# Adapter-IO4-test.net
KiCad netlist of a schematic drawn in EAGLE
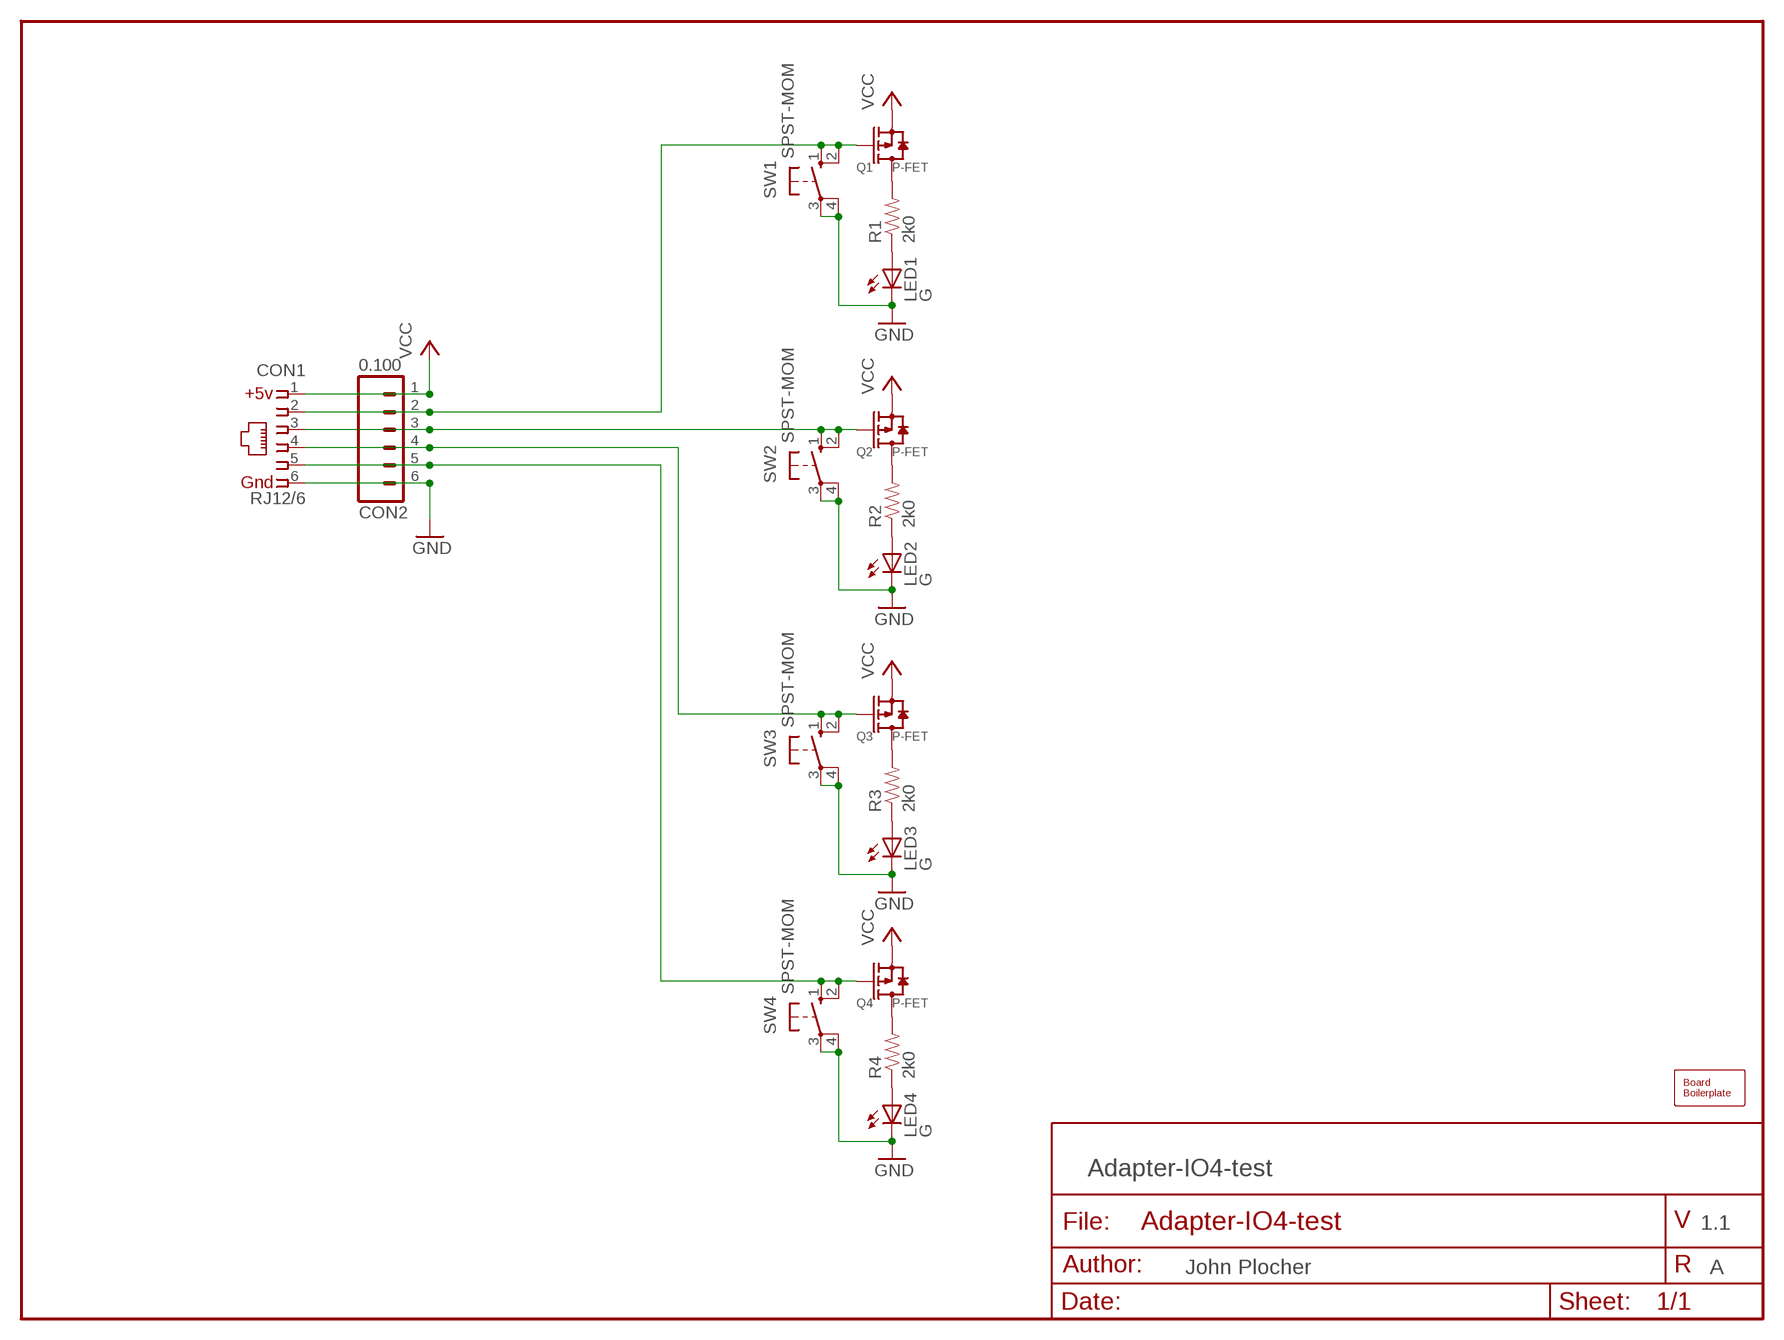
[diagram p0: schematic, sheet 1]

(export (version "E")
  (design (tool "Eeschema 10.0.6"))
  (components
    (comp (ref "BOARD1")
      (value "BOARD50X50-NOHOLES")
      (footprint "eagle-import:BOARD-SEEED5X5-NOHOLES")
      (libsource (lib "eagle-import") (part "BOARD50X50-NOHOLES"))
    )
    (comp (ref "CON1")
      (value "RJ12/6")
      (footprint "eagle-import:RJ25-INVERTED")
      (libsource (lib "eagle-import") (part "CONNECTOR-IO4INV"))
    )
    (comp (ref "CON2")
      (value "0.100")
      (footprint "eagle-import:1X06_LOCK")
      (libsource (lib "eagle-import") (part "CONNECTOR-M06LOCK"))
    )
    (comp (ref "LED1")
      (value "G")
      (footprint "eagle-import:0603-LED")
      (libsource (lib "eagle-import") (part "LED0603-LED"))
    )
    (comp (ref "LED2")
      (value "G")
      (footprint "eagle-import:0603-LED")
      (libsource (lib "eagle-import") (part "LED0603-LED"))
    )
    (comp (ref "LED3")
      (value "G")
      (footprint "eagle-import:0603-LED")
      (libsource (lib "eagle-import") (part "LED0603-LED"))
    )
    (comp (ref "LED4")
      (value "G")
      (footprint "eagle-import:0603-LED")
      (libsource (lib "eagle-import") (part "LED0603-LED"))
    )
    (comp (ref "Q1")
      (value "P-FET")
      (footprint "eagle-import:SOT23-3")
      (libsource (lib "eagle-import") (part "MOSFET-P"))
    )
    (comp (ref "Q2")
      (value "P-FET")
      (footprint "eagle-import:SOT23-3")
      (libsource (lib "eagle-import") (part "MOSFET-P"))
    )
    (comp (ref "Q3")
      (value "P-FET")
      (footprint "eagle-import:SOT23-3")
      (libsource (lib "eagle-import") (part "MOSFET-P"))
    )
    (comp (ref "Q4")
      (value "P-FET")
      (footprint "eagle-import:SOT23-3")
      (libsource (lib "eagle-import") (part "MOSFET-P"))
    )
    (comp (ref "R1")
      (value "2k0")
      (footprint "eagle-import:0603-RES")
      (libsource (lib "eagle-import") (part "R0603-RES"))
    )
    (comp (ref "R2")
      (value "2k0")
      (footprint "eagle-import:0603-RES")
      (libsource (lib "eagle-import") (part "R0603-RES"))
    )
    (comp (ref "R3")
      (value "2k0")
      (footprint "eagle-import:0603-RES")
      (libsource (lib "eagle-import") (part "R0603-RES"))
    )
    (comp (ref "R4")
      (value "2k0")
      (footprint "eagle-import:0603-RES")
      (libsource (lib "eagle-import") (part "R0603-RES"))
    )
    (comp (ref "SW1")
      (value "SPST-MOM")
      (footprint "eagle-import:B3F-10XX")
      (libsource (lib "eagle-import") (part "SWITCH-10-XX"))
    )
    (comp (ref "SW2")
      (value "SPST-MOM")
      (footprint "eagle-import:B3F-10XX")
      (libsource (lib "eagle-import") (part "SWITCH-10-XX"))
    )
    (comp (ref "SW3")
      (value "SPST-MOM")
      (footprint "eagle-import:B3F-10XX")
      (libsource (lib "eagle-import") (part "SWITCH-10-XX"))
    )
    (comp (ref "SW4")
      (value "SPST-MOM")
      (footprint "eagle-import:B3F-10XX")
      (libsource (lib "eagle-import") (part "SWITCH-10-XX"))
    )
  )
  (nets
    (net (code "1") (name "GND") (class "Default")
      (node (ref "CON1") (pin "6") (pinfunction "6_6") (pintype "power_in"))
      (node (ref "CON2") (pin "6") (pinfunction "6_6") (pintype "passive"))
      (node (ref "LED1") (pin "C") (pinfunction "C_C") (pintype "passive"))
      (node (ref "LED2") (pin "C") (pinfunction "C_C") (pintype "passive"))
      (node (ref "LED3") (pin "C") (pinfunction "C_C") (pintype "passive"))
      (node (ref "LED4") (pin "C") (pinfunction "C_C") (pintype "passive"))
      (node (ref "SW1") (pin "3") (pinfunction "P_3") (pintype "passive"))
      (node (ref "SW1") (pin "4") (pinfunction "P1_4") (pintype "passive"))
      (node (ref "SW2") (pin "3") (pinfunction "P_3") (pintype "passive"))
      (node (ref "SW2") (pin "4") (pinfunction "P1_4") (pintype "passive"))
      (node (ref "SW3") (pin "3") (pinfunction "P_3") (pintype "passive"))
      (node (ref "SW3") (pin "4") (pinfunction "P1_4") (pintype "passive"))
      (node (ref "SW4") (pin "3") (pinfunction "P_3") (pintype "passive"))
      (node (ref "SW4") (pin "4") (pinfunction "P1_4") (pintype "passive"))
    )
    (net (code "2") (name "Net-(LED1-PadA)") (class "Default")
      (node (ref "LED1") (pin "A") (pinfunction "A_A") (pintype "passive"))
      (node (ref "R1") (pin "1") (pinfunction "1_1") (pintype "passive"))
    )
    (net (code "3") (name "Net-(LED2-PadA)") (class "Default")
      (node (ref "LED2") (pin "A") (pinfunction "A_A") (pintype "passive"))
      (node (ref "R2") (pin "1") (pinfunction "1_1") (pintype "passive"))
    )
    (net (code "4") (name "Net-(LED3-PadA)") (class "Default")
      (node (ref "LED3") (pin "A") (pinfunction "A_A") (pintype "passive"))
      (node (ref "R3") (pin "1") (pinfunction "1_1") (pintype "passive"))
    )
    (net (code "5") (name "Net-(LED4-PadA)") (class "Default")
      (node (ref "LED4") (pin "A") (pinfunction "A_A") (pintype "passive"))
      (node (ref "R4") (pin "1") (pinfunction "1_1") (pintype "passive"))
    )
    (net (code "6") (name "Net-(Q1-D)") (class "Default")
      (node (ref "Q1") (pin "3") (pinfunction "D_3") (pintype "passive"))
      (node (ref "R1") (pin "2") (pinfunction "2_2") (pintype "passive"))
    )
    (net (code "7") (name "Net-(Q1-G)") (class "Default")
      (node (ref "CON1") (pin "2") (pinfunction "2_2") (pintype "passive"))
      (node (ref "CON2") (pin "2") (pinfunction "2_2") (pintype "passive"))
      (node (ref "Q1") (pin "1") (pinfunction "G_1") (pintype "passive"))
      (node (ref "SW1") (pin "1") (pinfunction "S_1") (pintype "passive"))
      (node (ref "SW1") (pin "2") (pinfunction "S1_2") (pintype "passive"))
    )
    (net (code "8") (name "Net-(Q2-D)") (class "Default")
      (node (ref "Q2") (pin "3") (pinfunction "D_3") (pintype "passive"))
      (node (ref "R2") (pin "2") (pinfunction "2_2") (pintype "passive"))
    )
    (net (code "9") (name "Net-(Q2-G)") (class "Default")
      (node (ref "CON1") (pin "3") (pinfunction "3_3") (pintype "passive"))
      (node (ref "CON2") (pin "3") (pinfunction "3_3") (pintype "passive"))
      (node (ref "Q2") (pin "1") (pinfunction "G_1") (pintype "passive"))
      (node (ref "SW2") (pin "1") (pinfunction "S_1") (pintype "passive"))
      (node (ref "SW2") (pin "2") (pinfunction "S1_2") (pintype "passive"))
    )
    (net (code "10") (name "Net-(Q3-D)") (class "Default")
      (node (ref "Q3") (pin "3") (pinfunction "D_3") (pintype "passive"))
      (node (ref "R3") (pin "2") (pinfunction "2_2") (pintype "passive"))
    )
    (net (code "11") (name "Net-(Q3-G)") (class "Default")
      (node (ref "CON1") (pin "4") (pinfunction "4_4") (pintype "passive"))
      (node (ref "CON2") (pin "4") (pinfunction "4_4") (pintype "passive"))
      (node (ref "Q3") (pin "1") (pinfunction "G_1") (pintype "passive"))
      (node (ref "SW3") (pin "1") (pinfunction "S_1") (pintype "passive"))
      (node (ref "SW3") (pin "2") (pinfunction "S1_2") (pintype "passive"))
    )
    (net (code "12") (name "Net-(Q4-D)") (class "Default")
      (node (ref "Q4") (pin "3") (pinfunction "D_3") (pintype "passive"))
      (node (ref "R4") (pin "2") (pinfunction "2_2") (pintype "passive"))
    )
    (net (code "13") (name "Net-(Q4-G)") (class "Default")
      (node (ref "CON1") (pin "5") (pinfunction "5_5") (pintype "passive"))
      (node (ref "CON2") (pin "5") (pinfunction "5_5") (pintype "passive"))
      (node (ref "Q4") (pin "1") (pinfunction "G_1") (pintype "passive"))
      (node (ref "SW4") (pin "1") (pinfunction "S_1") (pintype "passive"))
      (node (ref "SW4") (pin "2") (pinfunction "S1_2") (pintype "passive"))
    )
    (net (code "14") (name "VCC") (class "Default")
      (node (ref "CON1") (pin "1") (pinfunction "1_1") (pintype "power_in"))
      (node (ref "CON2") (pin "1") (pinfunction "1_1") (pintype "passive"))
      (node (ref "Q1") (pin "2") (pinfunction "S_2") (pintype "passive"))
      (node (ref "Q2") (pin "2") (pinfunction "S_2") (pintype "passive"))
      (node (ref "Q3") (pin "2") (pinfunction "S_2") (pintype "passive"))
      (node (ref "Q4") (pin "2") (pinfunction "S_2") (pintype "passive"))
    )
  )
)
